# Sheet5.net
KiCad netlist of a schematic drawn in Altium Designer
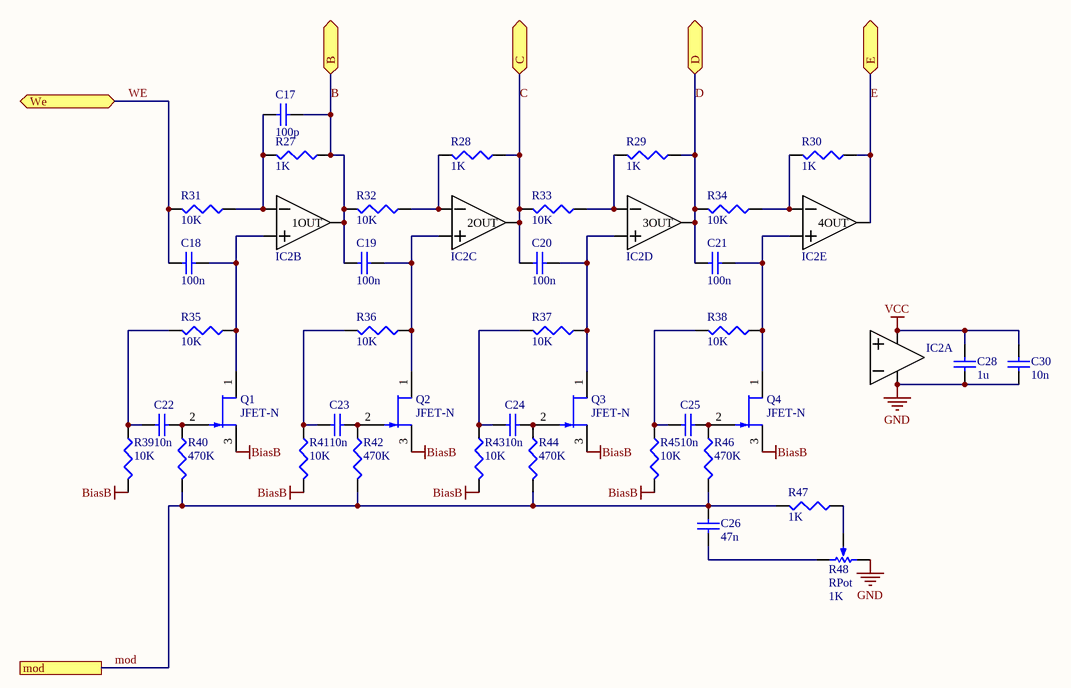
[diagram p0: Sheet5.SchDoc]

(export (version "E")
  (design (tool "Eeschema 10.0.6"))
  (components
    (comp (ref "C17")
      (value "100p")
      (footprint "C1206")
      (description "Capacitor (Semiconductor SIM Model)")
      (fields (field (name "Comment") "Cap Semi") (field (name "PUBLISHER") "Altium Limited"))
      (libsource (lib "Miscellaneous Devices") (part "Cap Semi"))
    )
    (comp (ref "C18")
      (value "100n")
      (footprint "C1206")
      (description "Capacitor (Semiconductor SIM Model)")
      (fields (field (name "Comment") "Cap Semi") (field (name "PUBLISHER") "Altium Limited"))
      (libsource (lib "Miscellaneous Devices") (part "Cap Semi"))
    )
    (comp (ref "C19")
      (value "100n")
      (footprint "C1206")
      (description "Capacitor (Semiconductor SIM Model)")
      (fields (field (name "Comment") "Cap Semi") (field (name "PUBLISHER") "Altium Limited"))
      (libsource (lib "Miscellaneous Devices") (part "Cap Semi"))
    )
    (comp (ref "C20")
      (value "100n")
      (footprint "C1206")
      (description "Capacitor (Semiconductor SIM Model)")
      (fields (field (name "Comment") "Cap Semi") (field (name "PUBLISHER") "Altium Limited"))
      (libsource (lib "Miscellaneous Devices") (part "Cap Semi"))
    )
    (comp (ref "C21")
      (value "100n")
      (footprint "C1206")
      (description "Capacitor (Semiconductor SIM Model)")
      (fields (field (name "Comment") "Cap Semi") (field (name "PUBLISHER") "Altium Limited"))
      (libsource (lib "Miscellaneous Devices") (part "Cap Semi"))
    )
    (comp (ref "C22")
      (value "10n")
      (footprint "C1206")
      (description "Capacitor (Semiconductor SIM Model)")
      (fields (field (name "Comment") "Cap Semi") (field (name "PUBLISHER") "Altium Limited"))
      (libsource (lib "Miscellaneous Devices") (part "Cap Semi"))
    )
    (comp (ref "C23")
      (value "10n")
      (footprint "C1206")
      (description "Capacitor (Semiconductor SIM Model)")
      (fields (field (name "Comment") "Cap Semi") (field (name "PUBLISHER") "Altium Limited"))
      (libsource (lib "Miscellaneous Devices") (part "Cap Semi"))
    )
    (comp (ref "C24")
      (value "10n")
      (footprint "C1206")
      (description "Capacitor (Semiconductor SIM Model)")
      (fields (field (name "Comment") "Cap Semi") (field (name "PUBLISHER") "Altium Limited"))
      (libsource (lib "Miscellaneous Devices") (part "Cap Semi"))
    )
    (comp (ref "C25")
      (value "10n")
      (footprint "C1206")
      (description "Capacitor (Semiconductor SIM Model)")
      (fields (field (name "Comment") "Cap Semi") (field (name "PUBLISHER") "Altium Limited"))
      (libsource (lib "Miscellaneous Devices") (part "Cap Semi"))
    )
    (comp (ref "C26")
      (value "47n")
      (footprint "C1206")
      (description "Capacitor (Semiconductor SIM Model)")
      (fields (field (name "Comment") "Cap Semi") (field (name "PUBLISHER") "Altium Limited"))
      (libsource (lib "Miscellaneous Devices") (part "Cap Semi"))
    )
    (comp (ref "C28")
      (value "1u")
      (footprint "C1206")
      (description "Capacitor (Semiconductor SIM Model)")
      (fields (field (name "Comment") "Cap Semi") (field (name "PUBLISHER") "Altium Limited"))
      (libsource (lib "Miscellaneous Devices") (part "Cap Semi"))
    )
    (comp (ref "C30")
      (value "10n")
      (footprint "C1206")
      (description "Capacitor (Semiconductor SIM Model)")
      (fields (field (name "Comment") "Cap Semi") (field (name "PUBLISHER") "Altium Limited"))
      (libsource (lib "Miscellaneous Devices") (part "Cap Semi"))
    )
    (comp (ref "IC2")
      (value "TL074A")
      (footprint "TL074A")
      (description "TL074A Op-Amp")
      (libsource (lib "lib1") (part "TL074A"))
    )
    (comp (ref "Q1")
      (value "JFET-N")
      (footprint "TO-254-AA")
      (description "N-Channel JFET")
      (fields (field (name "PUBLISHER") "Altium Limited"))
      (libsource (lib "Miscellaneous Devices") (part "JFET-N"))
    )
    (comp (ref "Q2")
      (value "JFET-N")
      (footprint "TO-254-AA")
      (description "N-Channel JFET")
      (fields (field (name "PUBLISHER") "Altium Limited"))
      (libsource (lib "Miscellaneous Devices") (part "JFET-N"))
    )
    (comp (ref "Q3")
      (value "JFET-N")
      (footprint "TO-254-AA")
      (description "N-Channel JFET")
      (fields (field (name "PUBLISHER") "Altium Limited"))
      (libsource (lib "Miscellaneous Devices") (part "JFET-N"))
    )
    (comp (ref "Q4")
      (value "JFET-N")
      (footprint "TO-254-AA")
      (description "N-Channel JFET")
      (fields (field (name "PUBLISHER") "Altium Limited"))
      (libsource (lib "Miscellaneous Devices") (part "JFET-N"))
    )
    (comp (ref "R27")
      (value "1K")
      (footprint "J1-0603")
      (description "Resistor")
      (fields (field (name "Comment") "Res3") (field (name "PUBLISHER") "Altium Limited"))
      (libsource (lib "Miscellaneous Devices") (part "Res3"))
    )
    (comp (ref "R28")
      (value "1K")
      (footprint "J1-0603")
      (description "Resistor")
      (fields (field (name "Comment") "Res3") (field (name "PUBLISHER") "Altium Limited"))
      (libsource (lib "Miscellaneous Devices") (part "Res3"))
    )
    (comp (ref "R29")
      (value "1K")
      (footprint "J1-0603")
      (description "Resistor")
      (fields (field (name "Comment") "Res3") (field (name "PUBLISHER") "Altium Limited"))
      (libsource (lib "Miscellaneous Devices") (part "Res3"))
    )
    (comp (ref "R30")
      (value "1K")
      (footprint "J1-0603")
      (description "Resistor")
      (fields (field (name "Comment") "Res3") (field (name "PUBLISHER") "Altium Limited"))
      (libsource (lib "Miscellaneous Devices") (part "Res3"))
    )
    (comp (ref "R31")
      (value "10K")
      (footprint "J1-0603")
      (description "Resistor")
      (fields (field (name "Comment") "Res3") (field (name "PUBLISHER") "Altium Limited"))
      (libsource (lib "Miscellaneous Devices") (part "Res3"))
    )
    (comp (ref "R32")
      (value "10K")
      (footprint "J1-0603")
      (description "Resistor")
      (fields (field (name "Comment") "Res3") (field (name "PUBLISHER") "Altium Limited"))
      (libsource (lib "Miscellaneous Devices") (part "Res3"))
    )
    (comp (ref "R33")
      (value "10K")
      (footprint "J1-0603")
      (description "Resistor")
      (fields (field (name "Comment") "Res3") (field (name "PUBLISHER") "Altium Limited"))
      (libsource (lib "Miscellaneous Devices") (part "Res3"))
    )
    (comp (ref "R34")
      (value "10K")
      (footprint "J1-0603")
      (description "Resistor")
      (fields (field (name "Comment") "Res3") (field (name "PUBLISHER") "Altium Limited"))
      (libsource (lib "Miscellaneous Devices") (part "Res3"))
    )
    (comp (ref "R35")
      (value "10K")
      (footprint "J1-0603")
      (description "Resistor")
      (fields (field (name "Comment") "Res3") (field (name "PUBLISHER") "Altium Limited"))
      (libsource (lib "Miscellaneous Devices") (part "Res3"))
    )
    (comp (ref "R36")
      (value "10K")
      (footprint "J1-0603")
      (description "Resistor")
      (fields (field (name "Comment") "Res3") (field (name "PUBLISHER") "Altium Limited"))
      (libsource (lib "Miscellaneous Devices") (part "Res3"))
    )
    (comp (ref "R37")
      (value "10K")
      (footprint "J1-0603")
      (description "Resistor")
      (fields (field (name "Comment") "Res3") (field (name "PUBLISHER") "Altium Limited"))
      (libsource (lib "Miscellaneous Devices") (part "Res3"))
    )
    (comp (ref "R38")
      (value "10K")
      (footprint "J1-0603")
      (description "Resistor")
      (fields (field (name "Comment") "Res3") (field (name "PUBLISHER") "Altium Limited"))
      (libsource (lib "Miscellaneous Devices") (part "Res3"))
    )
    (comp (ref "R39")
      (value "10K")
      (footprint "J1-0603")
      (description "Resistor")
      (fields (field (name "Comment") "Res3") (field (name "PUBLISHER") "Altium Limited"))
      (libsource (lib "Miscellaneous Devices") (part "Res3"))
    )
    (comp (ref "R40")
      (value "470K")
      (footprint "J1-0603")
      (description "Resistor")
      (fields (field (name "Comment") "Res3") (field (name "PUBLISHER") "Altium Limited"))
      (libsource (lib "Miscellaneous Devices") (part "Res3"))
    )
    (comp (ref "R41")
      (value "10K")
      (footprint "J1-0603")
      (description "Resistor")
      (fields (field (name "Comment") "Res3") (field (name "PUBLISHER") "Altium Limited"))
      (libsource (lib "Miscellaneous Devices") (part "Res3"))
    )
    (comp (ref "R42")
      (value "470K")
      (footprint "J1-0603")
      (description "Resistor")
      (fields (field (name "Comment") "Res3") (field (name "PUBLISHER") "Altium Limited"))
      (libsource (lib "Miscellaneous Devices") (part "Res3"))
    )
    (comp (ref "R43")
      (value "10K")
      (footprint "J1-0603")
      (description "Resistor")
      (fields (field (name "Comment") "Res3") (field (name "PUBLISHER") "Altium Limited"))
      (libsource (lib "Miscellaneous Devices") (part "Res3"))
    )
    (comp (ref "R44")
      (value "470K")
      (footprint "J1-0603")
      (description "Resistor")
      (fields (field (name "Comment") "Res3") (field (name "PUBLISHER") "Altium Limited"))
      (libsource (lib "Miscellaneous Devices") (part "Res3"))
    )
    (comp (ref "R45")
      (value "10K")
      (footprint "J1-0603")
      (description "Resistor")
      (fields (field (name "Comment") "Res3") (field (name "PUBLISHER") "Altium Limited"))
      (libsource (lib "Miscellaneous Devices") (part "Res3"))
    )
    (comp (ref "R46")
      (value "470K")
      (footprint "J1-0603")
      (description "Resistor")
      (fields (field (name "Comment") "Res3") (field (name "PUBLISHER") "Altium Limited"))
      (libsource (lib "Miscellaneous Devices") (part "Res3"))
    )
    (comp (ref "R47")
      (value "1K")
      (footprint "J1-0603")
      (description "Resistor")
      (fields (field (name "Comment") "Res3") (field (name "PUBLISHER") "Altium Limited"))
      (libsource (lib "Miscellaneous Devices") (part "Res3"))
    )
    (comp (ref "R48")
      (value "RPot")
      (footprint "VR5")
      (description "Potentiometer")
      (fields (field (name "ALTIUM_VALUE") "1K") (field (name "PUBLISHER") "Altium Limited"))
      (libsource (lib "Miscellaneous Devices") (part "RPot"))
    )
  )
  (nets
    (net (code "1") (name "/B") (class "Default")
      (node (ref "C17") (pin "1") (pinfunction "1_1") (pintype "passive"))
      (node (ref "C19") (pin "2") (pinfunction "2_2") (pintype "passive"))
      (node (ref "IC2") (pin "1") (pinfunction "1OUT_1") (pintype "passive"))
      (node (ref "R27") (pin "1") (pinfunction "1_1") (pintype "passive"))
      (node (ref "R32") (pin "2") (pinfunction "2_2") (pintype "passive"))
    )
    (net (code "2") (name "/C") (class "Default")
      (node (ref "C20") (pin "2") (pinfunction "2_2") (pintype "passive"))
      (node (ref "IC2") (pin "7") (pinfunction "2OUT_7") (pintype "passive"))
      (node (ref "R28") (pin "1") (pinfunction "1_1") (pintype "passive"))
      (node (ref "R33") (pin "2") (pinfunction "2_2") (pintype "passive"))
    )
    (net (code "3") (name "/D") (class "Default")
      (node (ref "C21") (pin "2") (pinfunction "2_2") (pintype "passive"))
      (node (ref "IC2") (pin "8") (pinfunction "3OUT_8") (pintype "passive"))
      (node (ref "R29") (pin "1") (pinfunction "1_1") (pintype "passive"))
      (node (ref "R34") (pin "2") (pinfunction "2_2") (pintype "passive"))
    )
    (net (code "4") (name "/E") (class "Default")
      (node (ref "IC2") (pin "14") (pinfunction "4OUT_14") (pintype "passive"))
      (node (ref "R30") (pin "1") (pinfunction "1_1") (pintype "passive"))
    )
    (net (code "5") (name "/WE") (class "Default")
      (node (ref "C18") (pin "2") (pinfunction "2_2") (pintype "passive"))
      (node (ref "R31") (pin "2") (pinfunction "2_2") (pintype "passive"))
    )
    (net (code "6") (name "/mod") (class "Default")
      (node (ref "C26") (pin "1") (pinfunction "1_1") (pintype "passive"))
      (node (ref "R40") (pin "2") (pinfunction "2_2") (pintype "passive"))
      (node (ref "R42") (pin "2") (pinfunction "2_2") (pintype "passive"))
      (node (ref "R44") (pin "2") (pinfunction "2_2") (pintype "passive"))
      (node (ref "R46") (pin "2") (pinfunction "2_2") (pintype "passive"))
      (node (ref "R47") (pin "2") (pinfunction "2_2") (pintype "passive"))
    )
    (net (code "7") (name "BiasB") (class "Default")
      (node (ref "Q1") (pin "3") (pinfunction "S_3") (pintype "passive"))
      (node (ref "Q2") (pin "3") (pinfunction "S_3") (pintype "passive"))
      (node (ref "Q3") (pin "3") (pinfunction "S_3") (pintype "passive"))
      (node (ref "Q4") (pin "3") (pinfunction "S_3") (pintype "passive"))
      (node (ref "R39") (pin "2") (pinfunction "2_2") (pintype "passive"))
      (node (ref "R41") (pin "2") (pinfunction "2_2") (pintype "passive"))
      (node (ref "R43") (pin "2") (pinfunction "2_2") (pintype "passive"))
      (node (ref "R45") (pin "2") (pinfunction "2_2") (pintype "passive"))
    )
    (net (code "8") (name "GND") (class "Default")
      (node (ref "C28") (pin "2") (pinfunction "2_2") (pintype "passive"))
      (node (ref "C30") (pin "2") (pinfunction "2_2") (pintype "passive"))
      (node (ref "IC2") (pin "11") (pinfunction "VCC-_11") (pintype "passive"))
      (node (ref "R48") (pin "1") (pinfunction "TOP_1") (pintype "passive"))
    )
    (net (code "9") (name "Net-(C22-Pad2)") (class "Default")
      (node (ref "C22") (pin "2") (pinfunction "2_2") (pintype "passive"))
      (node (ref "R35") (pin "2") (pinfunction "2_2") (pintype "passive"))
      (node (ref "R39") (pin "1") (pinfunction "1_1") (pintype "passive"))
    )
    (net (code "10") (name "Net-(C23-Pad2)") (class "Default")
      (node (ref "C23") (pin "2") (pinfunction "2_2") (pintype "passive"))
      (node (ref "R36") (pin "2") (pinfunction "2_2") (pintype "passive"))
      (node (ref "R41") (pin "1") (pinfunction "1_1") (pintype "passive"))
    )
    (net (code "11") (name "Net-(C24-Pad2)") (class "Default")
      (node (ref "C24") (pin "2") (pinfunction "2_2") (pintype "passive"))
      (node (ref "R37") (pin "2") (pinfunction "2_2") (pintype "passive"))
      (node (ref "R43") (pin "1") (pinfunction "1_1") (pintype "passive"))
    )
    (net (code "12") (name "Net-(C25-Pad2)") (class "Default")
      (node (ref "C25") (pin "2") (pinfunction "2_2") (pintype "passive"))
      (node (ref "R38") (pin "2") (pinfunction "2_2") (pintype "passive"))
      (node (ref "R45") (pin "1") (pinfunction "1_1") (pintype "passive"))
    )
    (net (code "13") (name "Net-(IC2B-1IN+)") (class "Default")
      (node (ref "C18") (pin "1") (pinfunction "1_1") (pintype "passive"))
      (node (ref "IC2") (pin "3") (pinfunction "1IN+_3") (pintype "passive"))
      (node (ref "Q1") (pin "1") (pinfunction "D_1") (pintype "passive"))
      (node (ref "R35") (pin "1") (pinfunction "1_1") (pintype "passive"))
    )
    (net (code "14") (name "Net-(IC2B-1IN-)") (class "Default")
      (node (ref "C17") (pin "2") (pinfunction "2_2") (pintype "passive"))
      (node (ref "IC2") (pin "2") (pinfunction "1IN-_2") (pintype "passive"))
      (node (ref "R27") (pin "2") (pinfunction "2_2") (pintype "passive"))
      (node (ref "R31") (pin "1") (pinfunction "1_1") (pintype "passive"))
    )
    (net (code "15") (name "Net-(IC2C-2IN+)") (class "Default")
      (node (ref "C19") (pin "1") (pinfunction "1_1") (pintype "passive"))
      (node (ref "IC2") (pin "5") (pinfunction "2IN+_5") (pintype "passive"))
      (node (ref "Q2") (pin "1") (pinfunction "D_1") (pintype "passive"))
      (node (ref "R36") (pin "1") (pinfunction "1_1") (pintype "passive"))
    )
    (net (code "16") (name "Net-(IC2C-2IN-)") (class "Default")
      (node (ref "IC2") (pin "6") (pinfunction "2IN-_6") (pintype "passive"))
      (node (ref "R28") (pin "2") (pinfunction "2_2") (pintype "passive"))
      (node (ref "R32") (pin "1") (pinfunction "1_1") (pintype "passive"))
    )
    (net (code "17") (name "Net-(IC2D-3IN+)") (class "Default")
      (node (ref "C20") (pin "1") (pinfunction "1_1") (pintype "passive"))
      (node (ref "IC2") (pin "10") (pinfunction "3IN+_10") (pintype "passive"))
      (node (ref "Q3") (pin "1") (pinfunction "D_1") (pintype "passive"))
      (node (ref "R37") (pin "1") (pinfunction "1_1") (pintype "passive"))
    )
    (net (code "18") (name "Net-(IC2D-3IN-)") (class "Default")
      (node (ref "IC2") (pin "9") (pinfunction "3IN-_9") (pintype "passive"))
      (node (ref "R29") (pin "2") (pinfunction "2_2") (pintype "passive"))
      (node (ref "R33") (pin "1") (pinfunction "1_1") (pintype "passive"))
    )
    (net (code "19") (name "Net-(IC2E-4IN+)") (class "Default")
      (node (ref "C21") (pin "1") (pinfunction "1_1") (pintype "passive"))
      (node (ref "IC2") (pin "12") (pinfunction "4IN+_12") (pintype "passive"))
      (node (ref "Q4") (pin "1") (pinfunction "D_1") (pintype "passive"))
      (node (ref "R38") (pin "1") (pinfunction "1_1") (pintype "passive"))
    )
    (net (code "20") (name "Net-(IC2E-4IN-)") (class "Default")
      (node (ref "IC2") (pin "13") (pinfunction "4IN-_13") (pintype "passive"))
      (node (ref "R30") (pin "2") (pinfunction "2_2") (pintype "passive"))
      (node (ref "R34") (pin "1") (pinfunction "1_1") (pintype "passive"))
    )
    (net (code "21") (name "Net-(Q1-G)") (class "Default")
      (node (ref "C22") (pin "1") (pinfunction "1_1") (pintype "passive"))
      (node (ref "Q1") (pin "2") (pinfunction "G_2") (pintype "passive"))
      (node (ref "R40") (pin "1") (pinfunction "1_1") (pintype "passive"))
    )
    (net (code "22") (name "Net-(Q2-G)") (class "Default")
      (node (ref "C23") (pin "1") (pinfunction "1_1") (pintype "passive"))
      (node (ref "Q2") (pin "2") (pinfunction "G_2") (pintype "passive"))
      (node (ref "R42") (pin "1") (pinfunction "1_1") (pintype "passive"))
    )
    (net (code "23") (name "Net-(Q3-G)") (class "Default")
      (node (ref "C24") (pin "1") (pinfunction "1_1") (pintype "passive"))
      (node (ref "Q3") (pin "2") (pinfunction "G_2") (pintype "passive"))
      (node (ref "R44") (pin "1") (pinfunction "1_1") (pintype "passive"))
    )
    (net (code "24") (name "Net-(Q4-G)") (class "Default")
      (node (ref "C25") (pin "1") (pinfunction "1_1") (pintype "passive"))
      (node (ref "Q4") (pin "2") (pinfunction "G_2") (pintype "passive"))
      (node (ref "R46") (pin "1") (pinfunction "1_1") (pintype "passive"))
    )
    (net (code "25") (name "Net-(R48-BOT)") (class "Default")
      (node (ref "C26") (pin "2") (pinfunction "2_2") (pintype "passive"))
      (node (ref "R48") (pin "2") (pinfunction "BOT_2") (pintype "passive"))
    )
    (net (code "26") (name "Net-(R48-TAP)") (class "Default")
      (node (ref "R47") (pin "1") (pinfunction "1_1") (pintype "passive"))
      (node (ref "R48") (pin "3") (pinfunction "TAP_3") (pintype "passive"))
    )
    (net (code "27") (name "VCC") (class "Default")
      (node (ref "C28") (pin "1") (pinfunction "1_1") (pintype "passive"))
      (node (ref "C30") (pin "1") (pinfunction "1_1") (pintype "passive"))
      (node (ref "IC2") (pin "4") (pinfunction "VCC+_4") (pintype "passive"))
    )
  )
)
